# ES_Daisy_Patch_SM_Init_Rev1.net
KiCad netlist of a schematic drawn in EAGLE
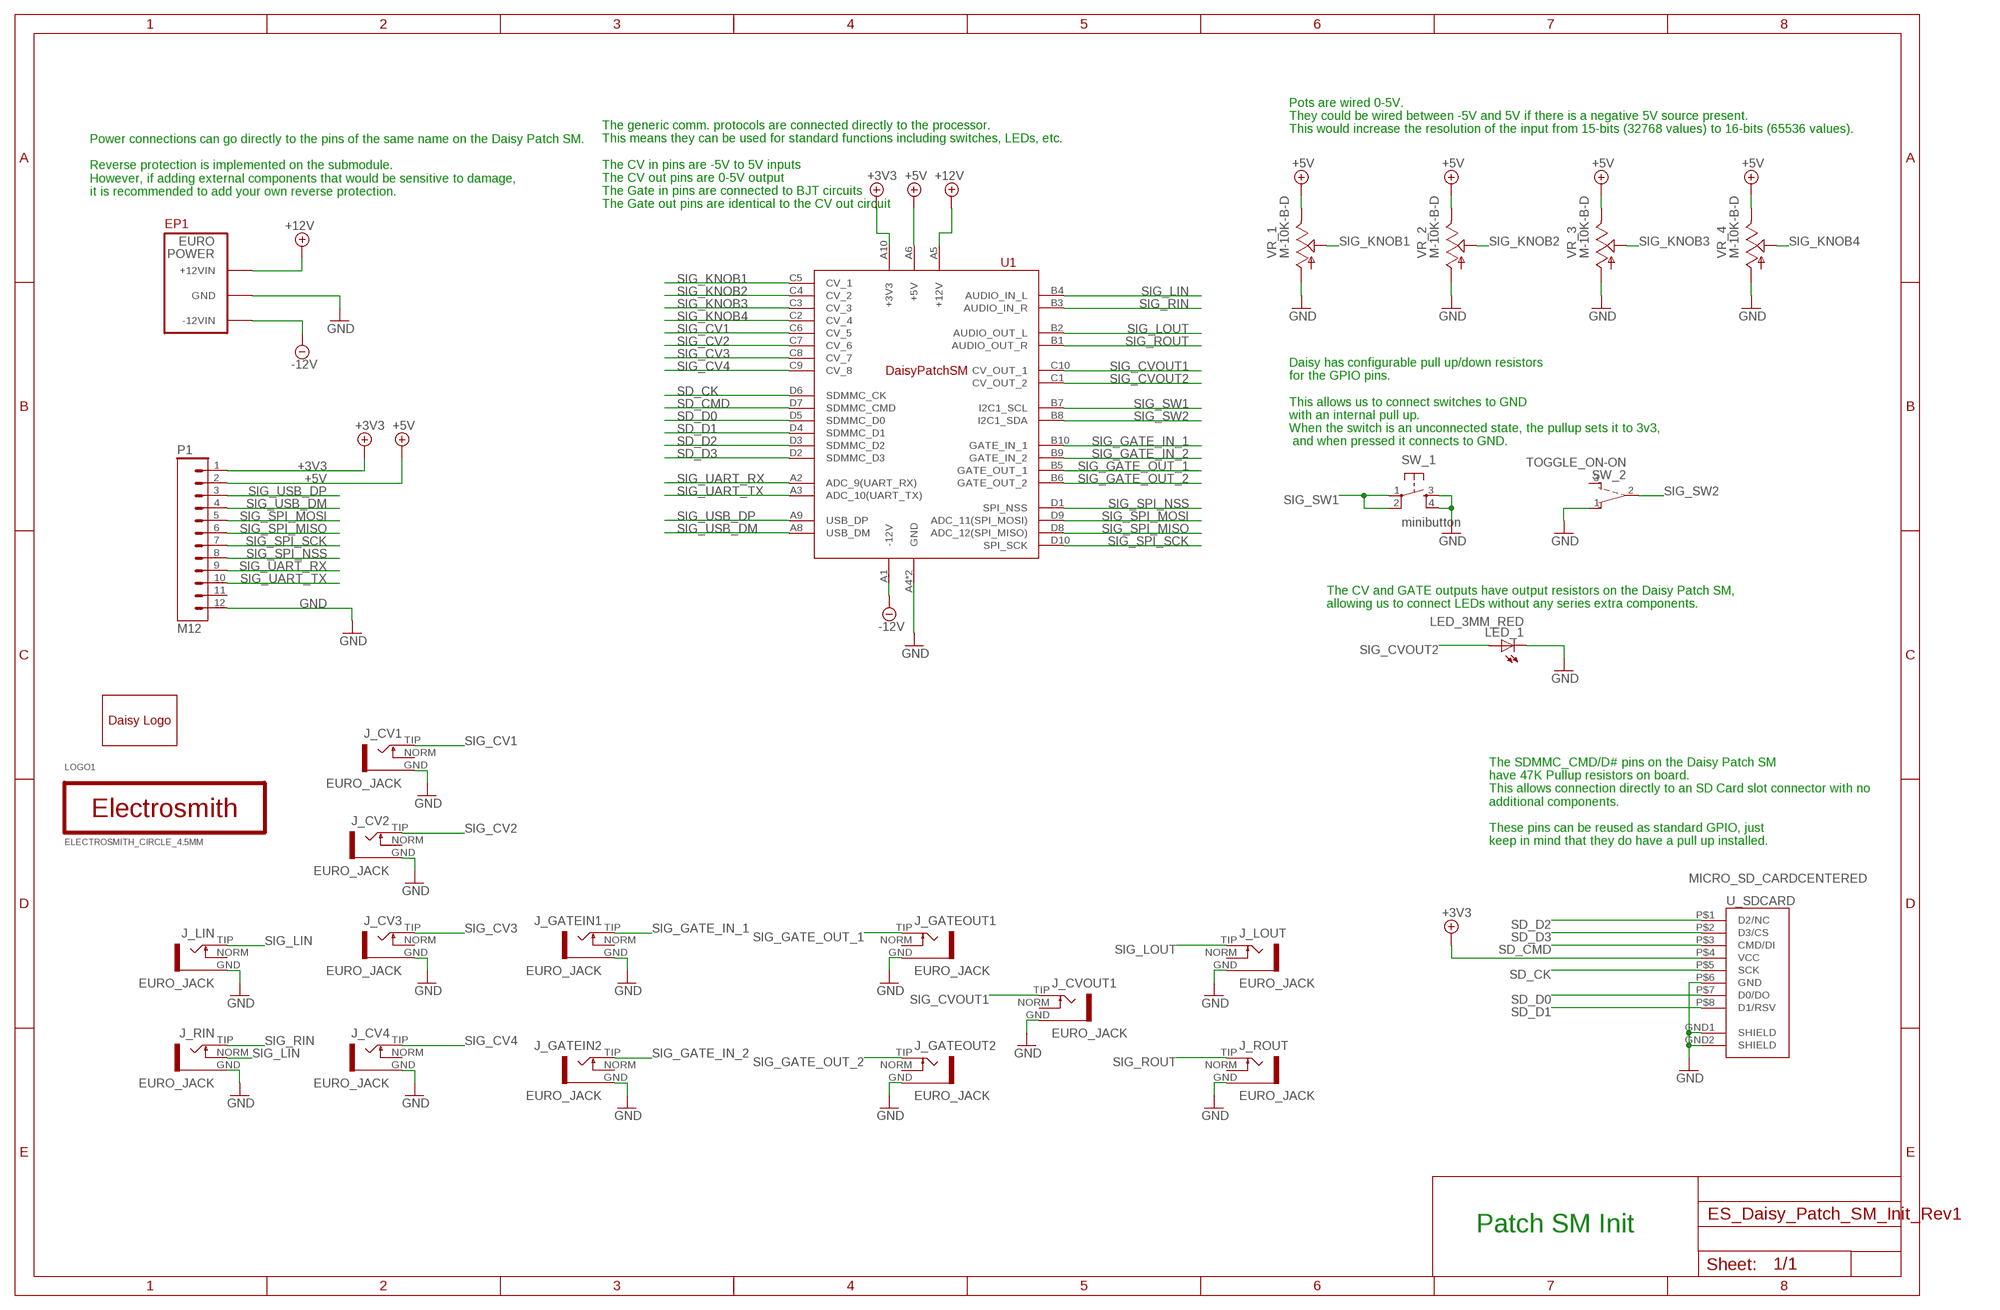
[diagram p0: schematic, sheet 1]

(export (version "E")
  (design (tool "Eeschema 10.0.6"))
  (components
    (comp (ref "EP1")
      (value "EURORACK_POWERLOCK")
      (footprint "eagle-import:EURORACK_POWER_SHROUD_LOCK")
      (fields (field (name "MPN") "2x5x.1-header"))
      (libsource (lib "eagle-import") (part "EURORACK_POWERLOCK"))
    )
    (comp (ref "J_CV1")
      (value "EURO_JACK")
      (footprint "eagle-import:S_JACK")
      (libsource (lib "eagle-import") (part "EURO_JACK"))
    )
    (comp (ref "J_CV2")
      (value "EURO_JACK")
      (footprint "eagle-import:S_JACK")
      (libsource (lib "eagle-import") (part "EURO_JACK"))
    )
    (comp (ref "J_CV3")
      (value "EURO_JACK")
      (footprint "eagle-import:S_JACK")
      (libsource (lib "eagle-import") (part "EURO_JACK"))
    )
    (comp (ref "J_CV4")
      (value "EURO_JACK")
      (footprint "eagle-import:S_JACK")
      (libsource (lib "eagle-import") (part "EURO_JACK"))
    )
    (comp (ref "J_CVOUT1")
      (value "EURO_JACK")
      (footprint "eagle-import:S_JACK")
      (libsource (lib "eagle-import") (part "EURO_JACK"))
    )
    (comp (ref "J_GATEIN1")
      (value "EURO_JACK")
      (footprint "eagle-import:S_JACK")
      (libsource (lib "eagle-import") (part "EURO_JACK"))
    )
    (comp (ref "J_GATEIN2")
      (value "EURO_JACK")
      (footprint "eagle-import:S_JACK")
      (libsource (lib "eagle-import") (part "EURO_JACK"))
    )
    (comp (ref "J_GATEOUT1")
      (value "EURO_JACK")
      (footprint "eagle-import:S_JACK")
      (libsource (lib "eagle-import") (part "EURO_JACK"))
    )
    (comp (ref "J_GATEOUT2")
      (value "EURO_JACK")
      (footprint "eagle-import:S_JACK")
      (libsource (lib "eagle-import") (part "EURO_JACK"))
    )
    (comp (ref "J_LIN")
      (value "EURO_JACK")
      (footprint "eagle-import:S_JACK")
      (libsource (lib "eagle-import") (part "EURO_JACK"))
    )
    (comp (ref "J_LOUT")
      (value "EURO_JACK")
      (footprint "eagle-import:S_JACK")
      (libsource (lib "eagle-import") (part "EURO_JACK"))
    )
    (comp (ref "J_RIN")
      (value "EURO_JACK")
      (footprint "eagle-import:S_JACK")
      (libsource (lib "eagle-import") (part "EURO_JACK"))
    )
    (comp (ref "J_ROUT")
      (value "EURO_JACK")
      (footprint "eagle-import:S_JACK")
      (libsource (lib "eagle-import") (part "EURO_JACK"))
    )
    (comp (ref "LED_1")
      (value "LED_3MM_RED")
      (footprint "eagle-import:LED")
      (libsource (lib "eagle-import") (part "LED_3MM_RED"))
    )
    (comp (ref "LOGO1")
      (value "ELECTROSMITH_CIRCLE_4.5MM")
      (footprint "eagle-import:ES_CIRCLE_4.5MM")
      (libsource (lib "eagle-import") (part "ELECTROSMITH_CIRCLE_4.5MM"))
    )
    (comp (ref "P1")
      (value "M12")
      (footprint "eagle-import:1X12")
      (libsource (lib "eagle-import") (part "M12"))
    )
    (comp (ref "SW_1")
      (value "minibutton")
      (footprint "eagle-import:TL1105SPF250Q_SILK")
      (fields (field (name "MPN") "TL1105SPF250Q"))
      (libsource (lib "eagle-import") (part "TAC_SWITCH_PTH_SILK"))
    )
    (comp (ref "SW_2")
      (value "TOGGLE_ON-ON")
      (footprint "eagle-import:TOGGLE_ON-ON")
      (libsource (lib "eagle-import") (part "TOGGLE_ON-ON"))
    )
    (comp (ref "U$2")
      (value "DAISYLOGO")
      (footprint "eagle-import:ES_DAISY_LOGO_1")
      (libsource (lib "eagle-import") (part "DAISYLOGO"))
    )
    (comp (ref "U1")
      (value "ES_DAISY_PATCH_SM_REV1")
      (footprint "eagle-import:ES_DAISY_PATCH_SM_REV1")
      (libsource (lib "eagle-import") (part "ES_DAISY_PATCH_SM_REV1"))
    )
    (comp (ref "U_SDCARD")
      (value "MICRO_SD_CARDCENTERED")
      (footprint "eagle-import:VERT_MICROSD_CENTERED")
      (libsource (lib "eagle-import") (part "MICRO_SD_CARDCENTERED"))
    )
    (comp (ref "VR_1")
      (value "M-10K-B-D")
      (footprint "eagle-import:9MM_SNAP-IN_POT_SILK")
      (libsource (lib "eagle-import") (part "POT_9MM_SNAP-IN__"))
    )
    (comp (ref "VR_2")
      (value "M-10K-B-D")
      (footprint "eagle-import:9MM_SNAP-IN_POT_SILK")
      (libsource (lib "eagle-import") (part "POT_9MM_SNAP-IN__"))
    )
    (comp (ref "VR_3")
      (value "M-10K-B-D")
      (footprint "eagle-import:9MM_SNAP-IN_POT_SILK")
      (libsource (lib "eagle-import") (part "POT_9MM_SNAP-IN__"))
    )
    (comp (ref "VR_4")
      (value "M-10K-B-D")
      (footprint "eagle-import:9MM_SNAP-IN_POT_SILK")
      (libsource (lib "eagle-import") (part "POT_9MM_SNAP-IN__"))
    )
  )
  (nets
    (net (code "1") (name "+3V3") (class "Default")
      (node (ref "P1") (pin "1") (pinfunction "1_1") (pintype "passive"))
      (node (ref "U1") (pin "A10") (pinfunction "+3V3_A10") (pintype "bidirectional"))
      (node (ref "U_SDCARD") (pin "P$4") (pinfunction "VCC_P$4") (pintype "bidirectional"))
    )
    (net (code "2") (name "+5V") (class "Default")
      (node (ref "P1") (pin "2") (pinfunction "2_2") (pintype "passive"))
      (node (ref "U1") (pin "A6") (pinfunction "+5V_A6") (pintype "bidirectional"))
      (node (ref "VR_1") (pin "3") (pinfunction "3_3") (pintype "passive"))
      (node (ref "VR_2") (pin "3") (pinfunction "3_3") (pintype "passive"))
      (node (ref "VR_3") (pin "3") (pinfunction "3_3") (pintype "passive"))
      (node (ref "VR_4") (pin "3") (pinfunction "3_3") (pintype "passive"))
    )
    (net (code "3") (name "+12V") (class "Default")
      (node (ref "EP1") (pin "POS1") (pinfunction "+12VIN_POS1") (pintype "bidirectional"))
      (node (ref "EP1") (pin "POS2") (pinfunction "+12VIN_POS2") (pintype "bidirectional"))
      (node (ref "U1") (pin "A5") (pinfunction "+12V_A5") (pintype "bidirectional"))
    )
    (net (code "4") (name "-12V") (class "Default")
      (node (ref "EP1") (pin "NEG1") (pinfunction "-12VIN_NEG1") (pintype "bidirectional"))
      (node (ref "EP1") (pin "NEG2") (pinfunction "-12VIN_NEG2") (pintype "bidirectional"))
      (node (ref "U1") (pin "A1") (pinfunction "-12V_A1") (pintype "bidirectional"))
    )
    (net (code "5") (name "/SD_CK") (class "Default")
      (node (ref "U1") (pin "D6") (pinfunction "SDMMC_CK_D6") (pintype "bidirectional"))
      (node (ref "U_SDCARD") (pin "P$5") (pinfunction "SCK_P$5") (pintype "bidirectional"))
    )
    (net (code "6") (name "/SD_CMD") (class "Default")
      (node (ref "U1") (pin "D7") (pinfunction "SDMMC_CMD_D7") (pintype "bidirectional"))
      (node (ref "U_SDCARD") (pin "P$3") (pinfunction "CMD/DI_P$3") (pintype "bidirectional"))
    )
    (net (code "7") (name "/SD_D0") (class "Default")
      (node (ref "U1") (pin "D5") (pinfunction "SDMMC_D0_D5") (pintype "bidirectional"))
      (node (ref "U_SDCARD") (pin "P$7") (pinfunction "D0/DO_P$7") (pintype "bidirectional"))
    )
    (net (code "8") (name "/SD_D1") (class "Default")
      (node (ref "U1") (pin "D4") (pinfunction "SDMMC_D1_D4") (pintype "bidirectional"))
      (node (ref "U_SDCARD") (pin "P$8") (pinfunction "D1/RSV_P$8") (pintype "bidirectional"))
    )
    (net (code "9") (name "/SD_D2") (class "Default")
      (node (ref "U1") (pin "D3") (pinfunction "SDMMC_D2_D3") (pintype "bidirectional"))
      (node (ref "U_SDCARD") (pin "P$1") (pinfunction "D2/NC_P$1") (pintype "bidirectional"))
    )
    (net (code "10") (name "/SD_D3") (class "Default")
      (node (ref "U1") (pin "D2") (pinfunction "SDMMC_D3_D2") (pintype "bidirectional"))
      (node (ref "U_SDCARD") (pin "P$2") (pinfunction "D3/CS_P$2") (pintype "bidirectional"))
    )
    (net (code "11") (name "/SIG_CV1") (class "Default")
      (node (ref "J_CV1") (pin "TIP") (pinfunction "TIP_TIP") (pintype "passive"))
      (node (ref "U1") (pin "C6") (pinfunction "CV_5_C6") (pintype "bidirectional"))
    )
    (net (code "12") (name "/SIG_CV2") (class "Default")
      (node (ref "J_CV2") (pin "TIP") (pinfunction "TIP_TIP") (pintype "passive"))
      (node (ref "U1") (pin "C7") (pinfunction "CV_6_C7") (pintype "bidirectional"))
    )
    (net (code "13") (name "/SIG_CV3") (class "Default")
      (node (ref "J_CV3") (pin "TIP") (pinfunction "TIP_TIP") (pintype "passive"))
      (node (ref "U1") (pin "C8") (pinfunction "CV_7_C8") (pintype "bidirectional"))
    )
    (net (code "14") (name "/SIG_CV4") (class "Default")
      (node (ref "J_CV4") (pin "TIP") (pinfunction "TIP_TIP") (pintype "passive"))
      (node (ref "U1") (pin "C9") (pinfunction "CV_8_C9") (pintype "bidirectional"))
    )
    (net (code "15") (name "/SIG_CVOUT1") (class "Default")
      (node (ref "J_CVOUT1") (pin "TIP") (pinfunction "TIP_TIP") (pintype "passive"))
      (node (ref "U1") (pin "C10") (pinfunction "CV_OUT_1_C10") (pintype "bidirectional"))
    )
    (net (code "16") (name "/SIG_CVOUT2") (class "Default")
      (node (ref "LED_1") (pin "A") (pinfunction "A_A") (pintype "passive"))
      (node (ref "U1") (pin "C1") (pinfunction "CV_OUT_2_C1") (pintype "bidirectional"))
    )
    (net (code "17") (name "/SIG_GATE_IN_1") (class "Default")
      (node (ref "J_GATEIN1") (pin "TIP") (pinfunction "TIP_TIP") (pintype "passive"))
      (node (ref "U1") (pin "B10") (pinfunction "GATE_IN_1_B10") (pintype "bidirectional"))
    )
    (net (code "18") (name "/SIG_GATE_IN_2") (class "Default")
      (node (ref "J_GATEIN2") (pin "TIP") (pinfunction "TIP_TIP") (pintype "passive"))
      (node (ref "U1") (pin "B9") (pinfunction "GATE_IN_2_B9") (pintype "bidirectional"))
    )
    (net (code "19") (name "/SIG_GATE_OUT_1") (class "Default")
      (node (ref "J_GATEOUT1") (pin "TIP") (pinfunction "TIP_TIP") (pintype "passive"))
      (node (ref "U1") (pin "B5") (pinfunction "GATE_OUT_1_B5") (pintype "bidirectional"))
    )
    (net (code "20") (name "/SIG_GATE_OUT_2") (class "Default")
      (node (ref "J_GATEOUT2") (pin "TIP") (pinfunction "TIP_TIP") (pintype "passive"))
      (node (ref "U1") (pin "B6") (pinfunction "GATE_OUT_2_B6") (pintype "bidirectional"))
    )
    (net (code "21") (name "/SIG_KNOB1") (class "Default")
      (node (ref "U1") (pin "C5") (pinfunction "CV_1_C5") (pintype "bidirectional"))
      (node (ref "VR_1") (pin "2") (pinfunction "2_2") (pintype "passive"))
    )
    (net (code "22") (name "/SIG_KNOB2") (class "Default")
      (node (ref "U1") (pin "C4") (pinfunction "CV_2_C4") (pintype "bidirectional"))
      (node (ref "VR_2") (pin "2") (pinfunction "2_2") (pintype "passive"))
    )
    (net (code "23") (name "/SIG_KNOB3") (class "Default")
      (node (ref "U1") (pin "C3") (pinfunction "CV_3_C3") (pintype "bidirectional"))
      (node (ref "VR_3") (pin "2") (pinfunction "2_2") (pintype "passive"))
    )
    (net (code "24") (name "/SIG_KNOB4") (class "Default")
      (node (ref "U1") (pin "C2") (pinfunction "CV_4_C2") (pintype "bidirectional"))
      (node (ref "VR_4") (pin "2") (pinfunction "2_2") (pintype "passive"))
    )
    (net (code "25") (name "/SIG_LIN") (class "Default")
      (node (ref "J_LIN") (pin "TIP") (pinfunction "TIP_TIP") (pintype "passive"))
      (node (ref "J_RIN") (pin "NORM") (pinfunction "NORM_NORM") (pintype "passive"))
      (node (ref "U1") (pin "B4") (pinfunction "AUDIO_IN_L_B4") (pintype "bidirectional"))
    )
    (net (code "26") (name "/SIG_LOUT") (class "Default")
      (node (ref "J_LOUT") (pin "TIP") (pinfunction "TIP_TIP") (pintype "passive"))
      (node (ref "U1") (pin "B2") (pinfunction "AUDIO_OUT_L_B2") (pintype "bidirectional"))
    )
    (net (code "27") (name "/SIG_RIN") (class "Default")
      (node (ref "J_RIN") (pin "TIP") (pinfunction "TIP_TIP") (pintype "passive"))
      (node (ref "U1") (pin "B3") (pinfunction "AUDIO_IN_R_B3") (pintype "bidirectional"))
    )
    (net (code "28") (name "/SIG_ROUT") (class "Default")
      (node (ref "J_ROUT") (pin "TIP") (pinfunction "TIP_TIP") (pintype "passive"))
      (node (ref "U1") (pin "B1") (pinfunction "AUDIO_OUT_R_B1") (pintype "bidirectional"))
    )
    (net (code "29") (name "/SIG_SPI_MISO") (class "Default")
      (node (ref "P1") (pin "6") (pinfunction "6_6") (pintype "passive"))
      (node (ref "U1") (pin "D8") (pinfunction "ADC_12(SPI_MISO)_D8") (pintype "bidirectional"))
    )
    (net (code "30") (name "/SIG_SPI_MOSI") (class "Default")
      (node (ref "P1") (pin "5") (pinfunction "5_5") (pintype "passive"))
      (node (ref "U1") (pin "D9") (pinfunction "ADC_11(SPI_MOSI)_D9") (pintype "bidirectional"))
    )
    (net (code "31") (name "/SIG_SPI_NSS") (class "Default")
      (node (ref "P1") (pin "8") (pinfunction "8_8") (pintype "passive"))
      (node (ref "U1") (pin "D1") (pinfunction "SPI_NSS_D1") (pintype "bidirectional"))
    )
    (net (code "32") (name "/SIG_SPI_SCK") (class "Default")
      (node (ref "P1") (pin "7") (pinfunction "7_7") (pintype "passive"))
      (node (ref "U1") (pin "D10") (pinfunction "SPI_SCK_D10") (pintype "bidirectional"))
    )
    (net (code "33") (name "/SIG_SW1") (class "Default")
      (node (ref "SW_1") (pin "1") (pinfunction "1_1") (pintype "passive"))
      (node (ref "SW_1") (pin "2") (pinfunction "2_2") (pintype "passive"))
      (node (ref "U1") (pin "B7") (pinfunction "I2C1_SCL_B7") (pintype "bidirectional"))
    )
    (net (code "34") (name "/SIG_SW2") (class "Default")
      (node (ref "SW_2") (pin "2") (pinfunction "P_2") (pintype "passive"))
      (node (ref "U1") (pin "B8") (pinfunction "I2C1_SDA_B8") (pintype "bidirectional"))
    )
    (net (code "35") (name "/SIG_UART_RX") (class "Default")
      (node (ref "P1") (pin "9") (pinfunction "9_9") (pintype "passive"))
      (node (ref "U1") (pin "A2") (pinfunction "ADC_9(UART_RX)_A2") (pintype "bidirectional"))
    )
    (net (code "36") (name "/SIG_UART_TX") (class "Default")
      (node (ref "P1") (pin "10") (pinfunction "10_10") (pintype "passive"))
      (node (ref "U1") (pin "A3") (pinfunction "ADC_10(UART_TX)_A3") (pintype "bidirectional"))
    )
    (net (code "37") (name "/SIG_USB_DM") (class "Default")
      (node (ref "P1") (pin "4") (pinfunction "4_4") (pintype "passive"))
      (node (ref "U1") (pin "A8") (pinfunction "USB_DM_A8") (pintype "bidirectional"))
    )
    (net (code "38") (name "/SIG_USB_DP") (class "Default")
      (node (ref "P1") (pin "3") (pinfunction "3_3") (pintype "passive"))
      (node (ref "U1") (pin "A9") (pinfunction "USB_DP_A9") (pintype "bidirectional"))
    )
    (net (code "39") (name "GND") (class "Default")
      (node (ref "EP1") (pin "GND1") (pinfunction "GND_GND1") (pintype "bidirectional"))
      (node (ref "EP1") (pin "GND2") (pinfunction "GND_GND2") (pintype "bidirectional"))
      (node (ref "EP1") (pin "GND3") (pinfunction "GND_GND3") (pintype "bidirectional"))
      (node (ref "EP1") (pin "GND4") (pinfunction "GND_GND4") (pintype "bidirectional"))
      (node (ref "EP1") (pin "GND5") (pinfunction "GND_GND5") (pintype "bidirectional"))
      (node (ref "EP1") (pin "GND6") (pinfunction "GND_GND6") (pintype "bidirectional"))
      (node (ref "J_CV1") (pin "GND") (pinfunction "GND_GND") (pintype "passive"))
      (node (ref "J_CV2") (pin "GND") (pinfunction "GND_GND") (pintype "passive"))
      (node (ref "J_CV3") (pin "GND") (pinfunction "GND_GND") (pintype "passive"))
      (node (ref "J_CV4") (pin "GND") (pinfunction "GND_GND") (pintype "passive"))
      (node (ref "J_CVOUT1") (pin "GND") (pinfunction "GND_GND") (pintype "passive"))
      (node (ref "J_GATEIN1") (pin "GND") (pinfunction "GND_GND") (pintype "passive"))
      (node (ref "J_GATEIN2") (pin "GND") (pinfunction "GND_GND") (pintype "passive"))
      (node (ref "J_GATEOUT1") (pin "GND") (pinfunction "GND_GND") (pintype "passive"))
      (node (ref "J_GATEOUT2") (pin "GND") (pinfunction "GND_GND") (pintype "passive"))
      (node (ref "J_LIN") (pin "GND") (pinfunction "GND_GND") (pintype "passive"))
      (node (ref "J_LOUT") (pin "GND") (pinfunction "GND_GND") (pintype "passive"))
      (node (ref "J_RIN") (pin "GND") (pinfunction "GND_GND") (pintype "passive"))
      (node (ref "J_ROUT") (pin "GND") (pinfunction "GND_GND") (pintype "passive"))
      (node (ref "LED_1") (pin "K") (pinfunction "C_K") (pintype "passive"))
      (node (ref "P1") (pin "12") (pinfunction "12_12") (pintype "passive"))
      (node (ref "SW_1") (pin "3") (pinfunction "3_3") (pintype "passive"))
      (node (ref "SW_1") (pin "4") (pinfunction "4_4") (pintype "passive"))
      (node (ref "SW_2") (pin "1") (pinfunction "O_1") (pintype "passive"))
      (node (ref "U1") (pin "A4") (pinfunction "GND_A4") (pintype "bidirectional"))
      (node (ref "U1") (pin "A7") (pinfunction "GND_A7") (pintype "bidirectional"))
      (node (ref "U_SDCARD") (pin "GND1") (pinfunction "SHIELD_GND1") (pintype "bidirectional"))
      (node (ref "U_SDCARD") (pin "GND2") (pinfunction "SHIELD_GND2") (pintype "bidirectional"))
      (node (ref "U_SDCARD") (pin "P$6") (pinfunction "GND_P$6") (pintype "bidirectional"))
      (node (ref "VR_1") (pin "1") (pinfunction "1_1") (pintype "passive"))
      (node (ref "VR_2") (pin "1") (pinfunction "1_1") (pintype "passive"))
      (node (ref "VR_3") (pin "1") (pinfunction "1_1") (pintype "passive"))
      (node (ref "VR_4") (pin "1") (pinfunction "1_1") (pintype "passive"))
    )
    (net (code "40") (name "unconnected-(J_CV1-PadNORM)") (class "Default")
      (node (ref "J_CV1") (pin "NORM") (pinfunction "NORM_NORM") (pintype "passive"))
    )
    (net (code "41") (name "unconnected-(J_CV2-PadNORM)") (class "Default")
      (node (ref "J_CV2") (pin "NORM") (pinfunction "NORM_NORM") (pintype "passive"))
    )
    (net (code "42") (name "unconnected-(J_CV3-PadNORM)") (class "Default")
      (node (ref "J_CV3") (pin "NORM") (pinfunction "NORM_NORM") (pintype "passive"))
    )
    (net (code "43") (name "unconnected-(J_CV4-PadNORM)") (class "Default")
      (node (ref "J_CV4") (pin "NORM") (pinfunction "NORM_NORM") (pintype "passive"))
    )
    (net (code "44") (name "unconnected-(J_CVOUT1-PadNORM)") (class "Default")
      (node (ref "J_CVOUT1") (pin "NORM") (pinfunction "NORM_NORM") (pintype "passive"))
    )
    (net (code "45") (name "unconnected-(J_GATEIN1-PadNORM)") (class "Default")
      (node (ref "J_GATEIN1") (pin "NORM") (pinfunction "NORM_NORM") (pintype "passive"))
    )
    (net (code "46") (name "unconnected-(J_GATEIN2-PadNORM)") (class "Default")
      (node (ref "J_GATEIN2") (pin "NORM") (pinfunction "NORM_NORM") (pintype "passive"))
    )
    (net (code "47") (name "unconnected-(J_GATEOUT1-PadNORM)") (class "Default")
      (node (ref "J_GATEOUT1") (pin "NORM") (pinfunction "NORM_NORM") (pintype "passive"))
    )
    (net (code "48") (name "unconnected-(J_GATEOUT2-PadNORM)") (class "Default")
      (node (ref "J_GATEOUT2") (pin "NORM") (pinfunction "NORM_NORM") (pintype "passive"))
    )
    (net (code "49") (name "unconnected-(J_LIN-PadNORM)") (class "Default")
      (node (ref "J_LIN") (pin "NORM") (pinfunction "NORM_NORM") (pintype "passive"))
    )
    (net (code "50") (name "unconnected-(J_LOUT-PadNORM)") (class "Default")
      (node (ref "J_LOUT") (pin "NORM") (pinfunction "NORM_NORM") (pintype "passive"))
    )
    (net (code "51") (name "unconnected-(J_ROUT-PadNORM)") (class "Default")
      (node (ref "J_ROUT") (pin "NORM") (pinfunction "NORM_NORM") (pintype "passive"))
    )
    (net (code "52") (name "unconnected-(P1-Pad11)") (class "Default")
      (node (ref "P1") (pin "11") (pinfunction "11_11") (pintype "passive"))
    )
    (net (code "53") (name "unconnected-(SW_2-S-Pad3)") (class "Default")
      (node (ref "SW_2") (pin "3") (pinfunction "S_3") (pintype "passive"))
    )
  )
)
